# Qwiic_Proximity_Sensor_-_VCNL4040.net
KiCad netlist of a schematic drawn in EAGLE
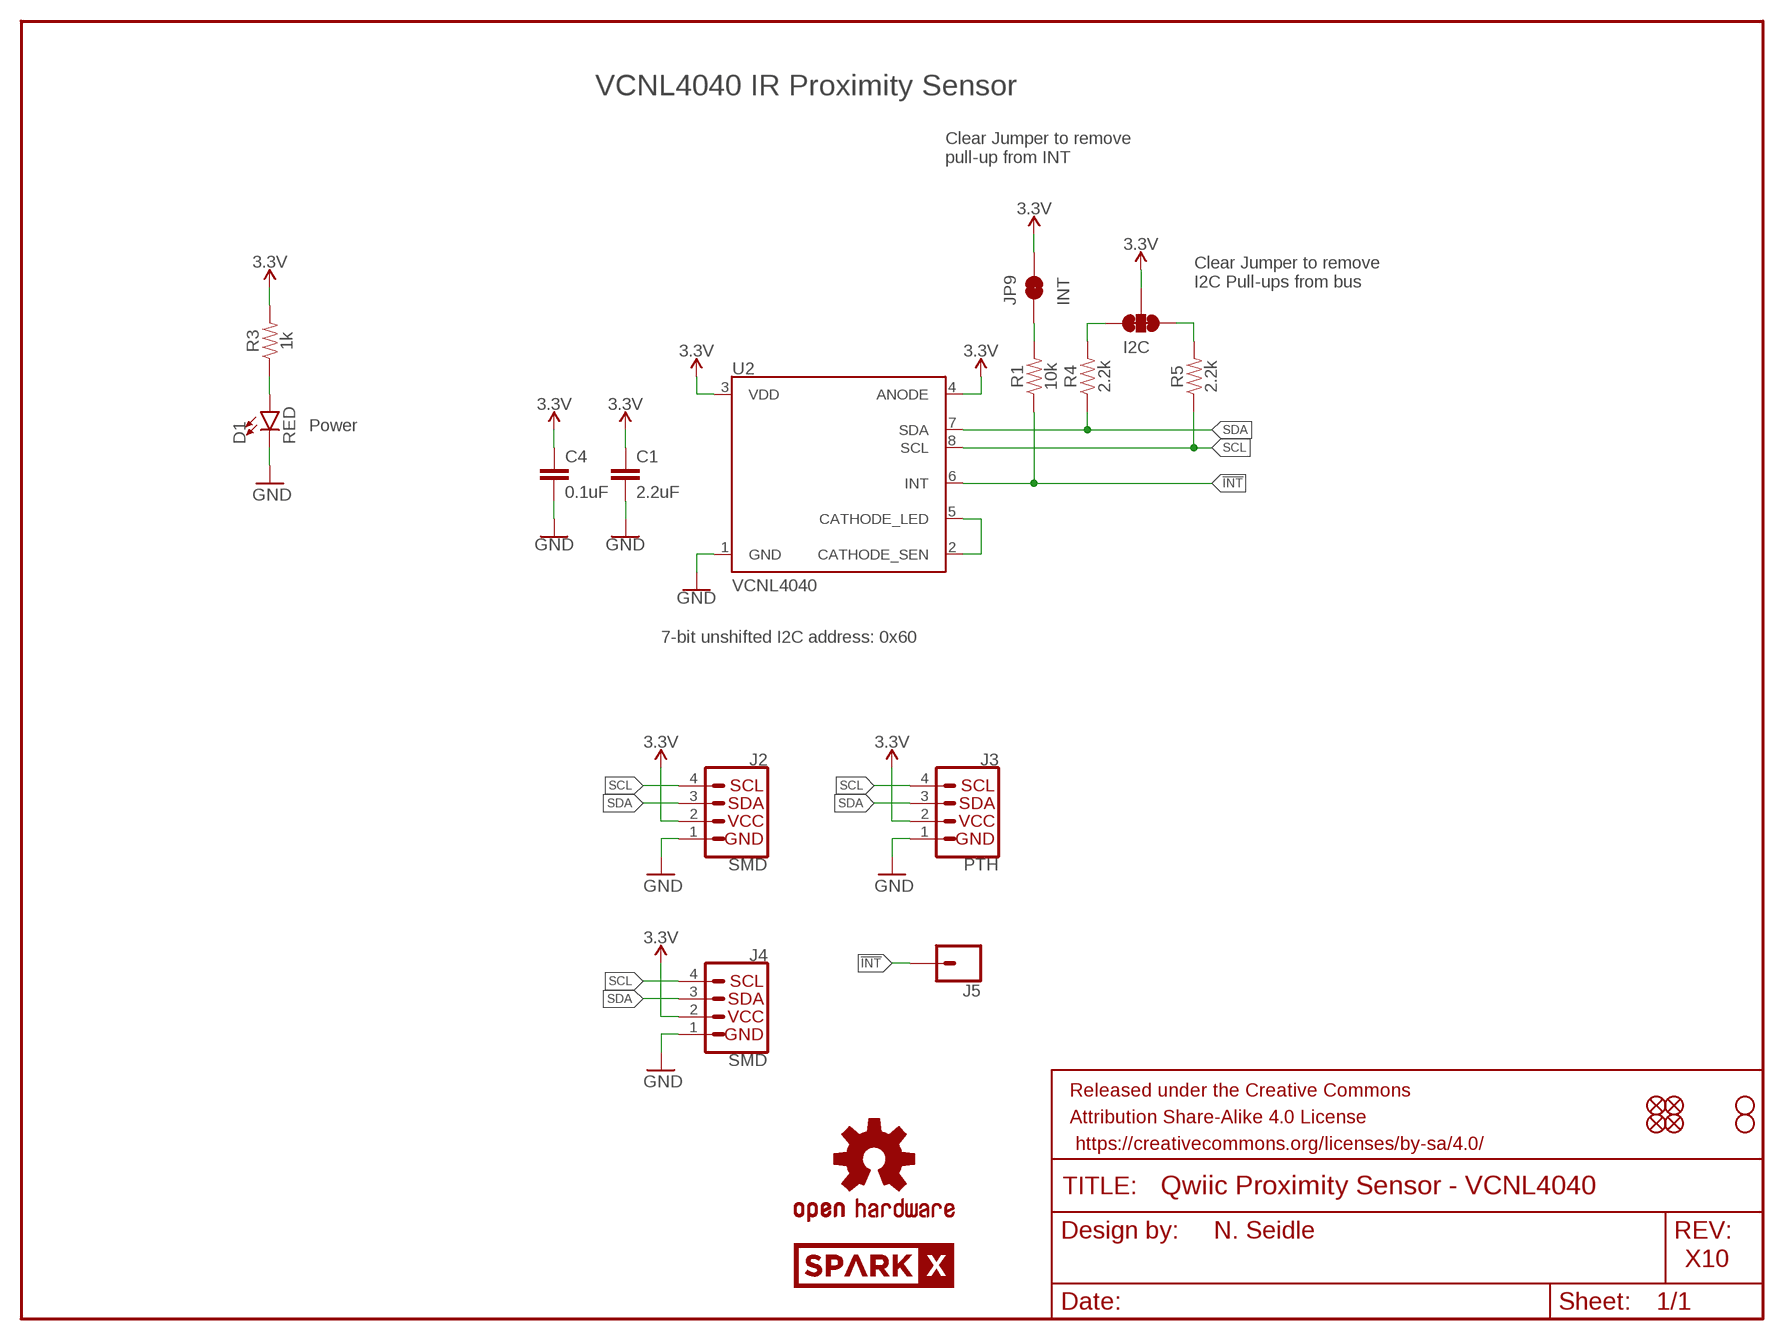
[diagram p0: schematic, sheet 1]

(export (version "E")
  (design (tool "Eeschema 10.0.6"))
  (components
    (comp (ref "C1")
      (value "2.2uF")
      (footprint "eagle-import:0603")
      (libsource (lib "eagle-import") (part "2.2UF-0603-10V-20%"))
    )
    (comp (ref "C4")
      (value "0.1uF")
      (footprint "eagle-import:0603")
      (libsource (lib "eagle-import") (part "0.1UF-0603-25V-(+80/-20%)"))
    )
    (comp (ref "D1")
      (value "RED")
      (footprint "eagle-import:LED-0603")
      (libsource (lib "eagle-import") (part "LED-RED0603"))
    )
    (comp (ref "FRAME1")
      (value "FRAME-LETTER")
      (footprint "eagle-import:CREATIVE_COMMONS")
      (libsource (lib "eagle-import") (part "FRAME-LETTER"))
    )
    (comp (ref "I2C")
      (value "JUMPER-SMT_3_2-NC_TRACE_SILK")
      (footprint "eagle-import:SMT-JUMPER_3_2-NC_TRACE_SILK")
      (libsource (lib "eagle-import") (part "JUMPER-SMT_3_2-NC_TRACE_SILK"))
    )
    (comp (ref "J2")
      (value "SMD")
      (footprint "eagle-import:1X04_1MM_RA")
      (libsource (lib "eagle-import") (part "I2C_STANDARDJS-1MM"))
    )
    (comp (ref "J3")
      (value "PTH")
      (footprint "eagle-import:1X04_NO_SILK")
      (libsource (lib "eagle-import") (part "I2C_STANDARD_NO_SILK"))
    )
    (comp (ref "J4")
      (value "SMD")
      (footprint "eagle-import:1X04_1MM_RA")
      (libsource (lib "eagle-import") (part "I2C_STANDARDJS-1MM"))
    )
    (comp (ref "J5")
      (value "CONN_01PTH_NO_SILK_YES_STOP")
      (footprint "eagle-import:1X01_NO_SILK")
      (libsource (lib "eagle-import") (part "CONN_01PTH_NO_SILK_YES_STOP"))
    )
    (comp (ref "JP1")
      (value "FIDUCIALUFIDUCIAL")
      (footprint "eagle-import:MICRO-FIDUCIAL")
      (libsource (lib "eagle-import") (part "FIDUCIALUFIDUCIAL"))
    )
    (comp (ref "JP2")
      (value "FIDUCIALUFIDUCIAL")
      (footprint "eagle-import:MICRO-FIDUCIAL")
      (libsource (lib "eagle-import") (part "FIDUCIALUFIDUCIAL"))
    )
    (comp (ref "JP3")
      (value "STAND-OFF")
      (footprint "eagle-import:STAND-OFF")
      (libsource (lib "eagle-import") (part "STAND-OFF"))
    )
    (comp (ref "JP4")
      (value "STAND-OFF")
      (footprint "eagle-import:STAND-OFF")
      (libsource (lib "eagle-import") (part "STAND-OFF"))
    )
    (comp (ref "JP5")
      (value "FIDUCIALUFIDUCIAL")
      (footprint "eagle-import:MICRO-FIDUCIAL")
      (libsource (lib "eagle-import") (part "FIDUCIALUFIDUCIAL"))
    )
    (comp (ref "JP6")
      (value "FIDUCIALUFIDUCIAL")
      (footprint "eagle-import:MICRO-FIDUCIAL")
      (libsource (lib "eagle-import") (part "FIDUCIALUFIDUCIAL"))
    )
    (comp (ref "JP9")
      (value "INT")
      (footprint "eagle-import:PAD-JUMPER-2-NC_BY_TRACE_YES_SILK")
      (libsource (lib "eagle-import") (part "JUMPER-PAD-2-NC_BY_TRACE"))
    )
    (comp (ref "LOGO1")
      (value "OSHW-LOGOMINI")
      (footprint "eagle-import:OSHW-LOGO-MINI")
      (libsource (lib "eagle-import") (part "OSHW-LOGOMINI"))
    )
    (comp (ref "R1")
      (value "10k")
      (footprint "eagle-import:0603")
      (libsource (lib "eagle-import") (part "10KOHM-0603-1/10W-1%"))
    )
    (comp (ref "R3")
      (value "1k")
      (footprint "eagle-import:0603")
      (libsource (lib "eagle-import") (part "1KOHM-0603-1/10W-1%"))
    )
    (comp (ref "R4")
      (value "2.2k")
      (footprint "eagle-import:0603")
      (libsource (lib "eagle-import") (part "2.2KOHM-0603-1/10W-1%"))
    )
    (comp (ref "R5")
      (value "2.2k")
      (footprint "eagle-import:0603")
      (libsource (lib "eagle-import") (part "2.2KOHM-0603-1/10W-1%"))
    )
    (comp (ref "U$1")
      (value "SPARKX-LOGO4")
      (footprint "eagle-import:SPARKX-MEDIUM")
      (libsource (lib "eagle-import") (part "SPARKX-LOGO4"))
    )
    (comp (ref "U$2")
      (value "SPARKX-LOGO4")
      (footprint "eagle-import:SPARKX-MEDIUM")
      (libsource (lib "eagle-import") (part "SPARKX-LOGO4"))
    )
    (comp (ref "U2")
      (value "VCNL4040")
      (footprint "eagle-import:VCNL4040")
      (libsource (lib "eagle-import") (part "VCNL4040"))
    )
  )
  (nets
    (net (code "1") (name "/~{INT}") (class "Default")
      (node (ref "J5") (pin "1") (pinfunction "1_1") (pintype "passive"))
      (node (ref "R1") (pin "1") (pinfunction "1_1") (pintype "passive"))
      (node (ref "U2") (pin "6") (pinfunction "INT_6") (pintype "bidirectional"))
    )
    (net (code "2") (name "3.3V") (class "Default")
      (node (ref "C1") (pin "1") (pinfunction "1_1") (pintype "passive"))
      (node (ref "C4") (pin "1") (pinfunction "1_1") (pintype "passive"))
      (node (ref "I2C") (pin "2") (pinfunction "2_2") (pintype "passive"))
      (node (ref "J2") (pin "2") (pinfunction "VCC_2") (pintype "power_in"))
      (node (ref "J3") (pin "2") (pinfunction "VCC_2") (pintype "power_in"))
      (node (ref "J4") (pin "2") (pinfunction "VCC_2") (pintype "power_in"))
      (node (ref "JP9") (pin "2") (pinfunction "2_2") (pintype "passive"))
      (node (ref "R3") (pin "2") (pinfunction "2_2") (pintype "passive"))
      (node (ref "U2") (pin "3") (pinfunction "VDD_3") (pintype "bidirectional"))
      (node (ref "U2") (pin "4") (pinfunction "ANODE_4") (pintype "bidirectional"))
    )
    (net (code "3") (name "GND") (class "Default")
      (node (ref "C1") (pin "2") (pinfunction "2_2") (pintype "passive"))
      (node (ref "C4") (pin "2") (pinfunction "2_2") (pintype "passive"))
      (node (ref "D1") (pin "C") (pinfunction "C_C") (pintype "passive"))
      (node (ref "J2") (pin "1") (pinfunction "GND_1") (pintype "power_in"))
      (node (ref "J3") (pin "1") (pinfunction "GND_1") (pintype "power_in"))
      (node (ref "J4") (pin "1") (pinfunction "GND_1") (pintype "power_in"))
      (node (ref "U2") (pin "1") (pinfunction "GND_1") (pintype "bidirectional"))
    )
    (net (code "4") (name "Net-(D1-PadA)") (class "Default")
      (node (ref "D1") (pin "A") (pinfunction "A_A") (pintype "passive"))
      (node (ref "R3") (pin "1") (pinfunction "1_1") (pintype "passive"))
    )
    (net (code "5") (name "Net-(I2C-Pad1)") (class "Default")
      (node (ref "I2C") (pin "1") (pinfunction "1_1") (pintype "passive"))
      (node (ref "R5") (pin "2") (pinfunction "2_2") (pintype "passive"))
    )
    (net (code "6") (name "Net-(I2C-Pad3)") (class "Default")
      (node (ref "I2C") (pin "3") (pinfunction "3_3") (pintype "passive"))
      (node (ref "R4") (pin "2") (pinfunction "2_2") (pintype "passive"))
    )
    (net (code "7") (name "Net-(JP9-Pad1)") (class "Default")
      (node (ref "JP9") (pin "1") (pinfunction "1_1") (pintype "passive"))
      (node (ref "R1") (pin "2") (pinfunction "2_2") (pintype "passive"))
    )
    (net (code "8") (name "Net-(U2-CATHODE_LED)") (class "Default")
      (node (ref "U2") (pin "2") (pinfunction "CATHODE_SEN_2") (pintype "bidirectional"))
      (node (ref "U2") (pin "5") (pinfunction "CATHODE_LED_5") (pintype "bidirectional"))
    )
    (net (code "9") (name "SCL") (class "Default")
      (node (ref "J2") (pin "4") (pinfunction "SCL_4") (pintype "passive"))
      (node (ref "J3") (pin "4") (pinfunction "SCL_4") (pintype "passive"))
      (node (ref "J4") (pin "4") (pinfunction "SCL_4") (pintype "passive"))
      (node (ref "R5") (pin "1") (pinfunction "1_1") (pintype "passive"))
      (node (ref "U2") (pin "8") (pinfunction "SCL_8") (pintype "bidirectional"))
    )
    (net (code "10") (name "SDA") (class "Default")
      (node (ref "J2") (pin "3") (pinfunction "SDA_3") (pintype "passive"))
      (node (ref "J3") (pin "3") (pinfunction "SDA_3") (pintype "passive"))
      (node (ref "J4") (pin "3") (pinfunction "SDA_3") (pintype "passive"))
      (node (ref "R4") (pin "1") (pinfunction "1_1") (pintype "passive"))
      (node (ref "U2") (pin "7") (pinfunction "SDA_7") (pintype "bidirectional"))
    )
  )
)
